# proj_arhipov_reset_swd.net
KiCad netlist of a schematic drawn in Altium Designer
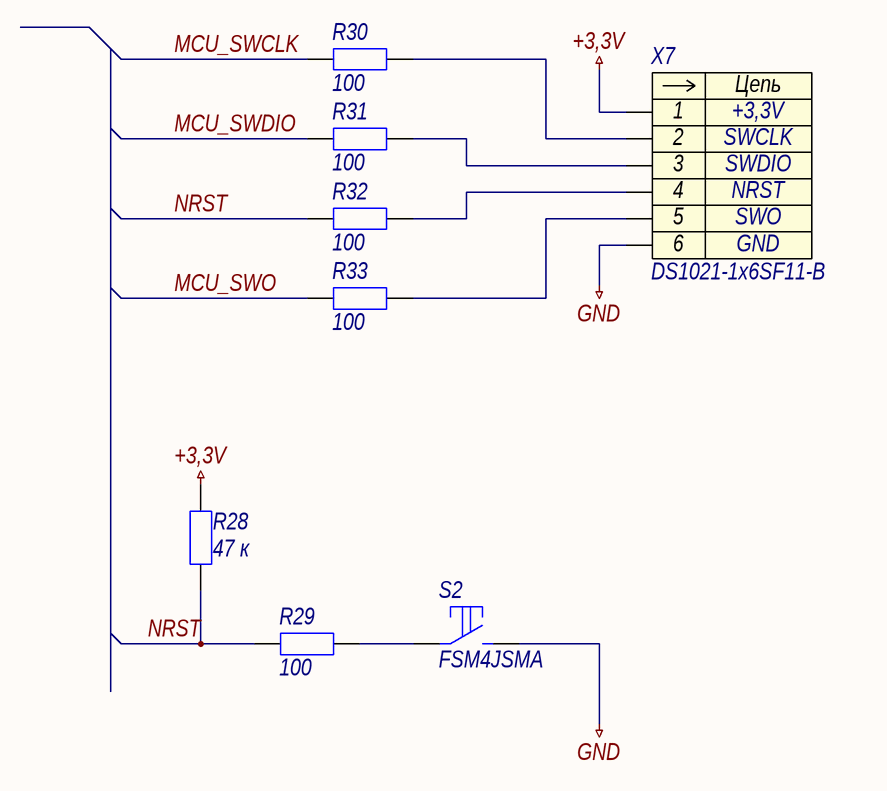
[diagram p0: proj_arhipov_reset_swd.SchDoc]

(export (version "E")
  (design (tool "Eeschema 10.0.6"))
  (components
    (comp (ref "R28")
      (value "47 к")
      (footprint "R0603")
      (description "=Описание")
      (libsource (lib "Database_Students") (part "RESISTOR-COMMON"))
    )
    (comp (ref "R29")
      (value "100")
      (footprint "R0603")
      (description "=Описание")
      (libsource (lib "Database_Students") (part "RESISTOR-COMMON"))
    )
    (comp (ref "R30")
      (value "100")
      (footprint "R0603")
      (description "=Описание")
      (libsource (lib "Database_Students") (part "RESISTOR-COMMON"))
    )
    (comp (ref "R31")
      (value "100")
      (footprint "R0603")
      (description "=Описание")
      (libsource (lib "Database_Students") (part "RESISTOR-COMMON"))
    )
    (comp (ref "R32")
      (value "100")
      (footprint "R0603")
      (description "=Описание")
      (libsource (lib "Database_Students") (part "RESISTOR-COMMON"))
    )
    (comp (ref "R33")
      (value "100")
      (footprint "R0603")
      (description "=Описание")
      (libsource (lib "Database_Students") (part "RESISTOR-COMMON"))
    )
    (comp (ref "S2")
      (value "FSM4JSMA")
      (footprint "FSM4JSMA")
      (description "=Описание")
      (libsource (lib "Database_Students") (part "BUTTON"))
    )
    (comp (ref "X7")
      (value "DS1021-1x6SF11-B")
      (footprint "DS1021-1X6SF11-B")
      (description "=Описание")
      (libsource (lib "Database_Students") (part "HEADER-6-PLG"))
    )
  )
  (nets
    (net (code "1") (name "+3,3V") (class "Default")
      (node (ref "R28") (pin "2") (pinfunction "2_2") (pintype "passive"))
      (node (ref "X7") (pin "1") (pinfunction "1_1") (pintype "passive"))
    )
    (net (code "2") (name "/MCU_SWCLK") (class "Default")
      (node (ref "R30") (pin "1") (pinfunction "1_1") (pintype "passive"))
    )
    (net (code "3") (name "/MCU_SWDIO") (class "Default")
      (node (ref "R31") (pin "1") (pinfunction "1_1") (pintype "passive"))
    )
    (net (code "4") (name "/MCU_SWO") (class "Default")
      (node (ref "R33") (pin "1") (pinfunction "1_1") (pintype "passive"))
    )
    (net (code "5") (name "/NRST") (class "Default")
      (node (ref "R28") (pin "1") (pinfunction "1_1") (pintype "passive"))
      (node (ref "R29") (pin "1") (pinfunction "1_1") (pintype "passive"))
      (node (ref "R32") (pin "1") (pinfunction "1_1") (pintype "passive"))
    )
    (net (code "6") (name "GND") (class "Default")
      (node (ref "S2") (pin "2") (pinfunction "2_2") (pintype "passive"))
      (node (ref "X7") (pin "6") (pinfunction "6_6") (pintype "passive"))
    )
    (net (code "7") (name "Net-(R29-Pad2)") (class "Default")
      (node (ref "R29") (pin "2") (pinfunction "2_2") (pintype "passive"))
      (node (ref "S2") (pin "1") (pinfunction "1_1") (pintype "passive"))
    )
    (net (code "8") (name "Net-(R30-Pad2)") (class "Default")
      (node (ref "R30") (pin "2") (pinfunction "2_2") (pintype "passive"))
      (node (ref "X7") (pin "2") (pinfunction "2_2") (pintype "passive"))
    )
    (net (code "9") (name "Net-(R31-Pad2)") (class "Default")
      (node (ref "R31") (pin "2") (pinfunction "2_2") (pintype "passive"))
      (node (ref "X7") (pin "3") (pinfunction "3_3") (pintype "passive"))
    )
    (net (code "10") (name "Net-(R32-Pad2)") (class "Default")
      (node (ref "R32") (pin "2") (pinfunction "2_2") (pintype "passive"))
      (node (ref "X7") (pin "4") (pinfunction "4_4") (pintype "passive"))
    )
    (net (code "11") (name "Net-(R33-Pad2)") (class "Default")
      (node (ref "R33") (pin "2") (pinfunction "2_2") (pintype "passive"))
      (node (ref "X7") (pin "5") (pinfunction "5_5") (pintype "passive"))
    )
  )
)
